# SCH_05_USB_To_TTL.net
KiCad netlist of a schematic drawn in Altium Designer
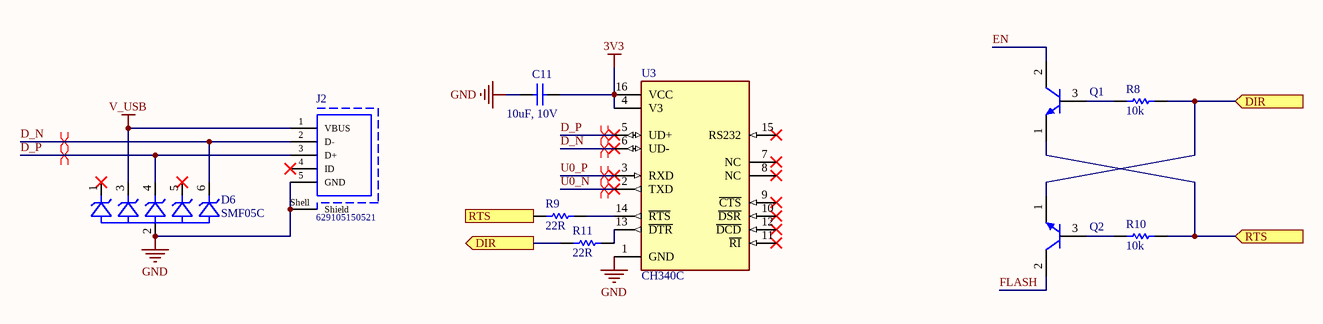
[diagram p0: SCH_05_USB_To_TTL.SchDoc]

(export (version "E")
  (design (tool "Eeschema 10.0.6"))
  (components
    (comp (ref "C11")
      (value "10uF, 10V")
      (footprint "WCAP-CSGP_0603_H=0.8mm_Reflow")
      (description "WCAP-CSGP Multilayer Ceramic Chip Capacitor, General Purpose, size 0603, X7R, 100nF, 10V")
      (fields
        (field (name "MANUFACTURER PART NUMBER") "885012206020")
        (field (name "MANUFACTURER") "Wurth Elektronik")
      )
      (libsource (lib "Altium_WCAP-CSGP (rev20a)") (part "885012206020"))
    )
    (comp (ref "D6")
      (value "SMF05C")
      (footprint "SC70-6")
      (description "12.5V Clamp 8A (8/20Âµs) Ipp Tvs Diode Surface Mount SC-88/SC70-6/SOT-363")
      (fields (field (name "MF") "ProTek Devices"))
      (libsource (lib "SMF05C") (part "SMF05C"))
    )
    (comp (ref "J2")
      (value "629105150521")
      (footprint "629105150521")
      (description "Micro USB 2.0 Type B Receptacle WR-COM, Horizontal, SMT, with Pegs, High Current at Pin 1 & Pin 5")
      (fields (field (name "PUBLISHER") "Wurth Elektronik"))
      (libsource (lib "ALTIUM-WR-COM_USB_20-rev18d") (part "629105150521"))
    )
    (comp (ref "Q1")
      (value "C1815")
      (footprint "SOT23B")
      (description "NPN Bipolar Transistor")
      (libsource (lib "PIF_Library") (part "C1815"))
    )
    (comp (ref "Q2")
      (value "C1815")
      (footprint "SOT23B")
      (description "NPN Bipolar Transistor")
      (libsource (lib "PIF_Library") (part "C1815"))
    )
    (comp (ref "R8")
      (value "10k")
      (footprint "RES-SM-0603")
      (description "Resistor")
      (fields (field (name "Comment") "RESISTOR SMD"))
      (libsource (lib "PIF_Library") (part "RESISTOR SMD"))
    )
    (comp (ref "R9")
      (value "22R")
      (footprint "RES-SM-0603")
      (description "Resistor")
      (fields (field (name "Comment") "RESISTOR SMD"))
      (libsource (lib "PIF_Library") (part "RESISTOR SMD"))
    )
    (comp (ref "R10")
      (value "10k")
      (footprint "RES-SM-0603")
      (description "Resistor")
      (fields (field (name "Comment") "RESISTOR SMD"))
      (libsource (lib "PIF_Library") (part "RESISTOR SMD"))
    )
    (comp (ref "R11")
      (value "22R")
      (footprint "RES-SM-0603")
      (description "Resistor")
      (fields (field (name "Comment") "RESISTOR SMD"))
      (libsource (lib "PIF_Library") (part "RESISTOR SMD"))
    )
    (comp (ref "U3")
      (value "CH340C")
      (footprint "SOIC127P600X180-16N")
      (libsource (lib "CH340") (part "CH340C"))
    )
  )
  (nets
    (net (code "1") (name "/DIR") (class "Default")
      (node (ref "Q2") (pin "1") (pinfunction "E_1") (pintype "passive"))
      (node (ref "R11") (pin "1") (pinfunction "1_1") (pintype "passive"))
      (node (ref "R8") (pin "2") (pinfunction "2_2") (pintype "passive"))
    )
    (net (code "2") (name "/D_N") (class "Default")
      (node (ref "D6") (pin "6") (pinfunction "C5_6") (pintype "passive"))
      (node (ref "J2") (pin "2") (pinfunction "D-_2") (pintype "passive"))
      (node (ref "U3") (pin "6") (pinfunction "UD-_6") (pintype "bidirectional"))
    )
    (net (code "3") (name "/D_P") (class "Default")
      (node (ref "D6") (pin "4") (pinfunction "C3_4") (pintype "passive"))
      (node (ref "J2") (pin "3") (pinfunction "D+_3") (pintype "passive"))
      (node (ref "U3") (pin "5") (pinfunction "UD+_5") (pintype "bidirectional"))
    )
    (net (code "4") (name "/EN") (class "Default")
      (node (ref "Q1") (pin "2") (pinfunction "C_2") (pintype "passive"))
    )
    (net (code "5") (name "/FLASH") (class "Default")
      (node (ref "Q2") (pin "2") (pinfunction "C_2") (pintype "passive"))
    )
    (net (code "6") (name "/RTS") (class "Default")
      (node (ref "Q1") (pin "1") (pinfunction "E_1") (pintype "passive"))
      (node (ref "R10") (pin "2") (pinfunction "2_2") (pintype "passive"))
      (node (ref "R9") (pin "1") (pinfunction "1_1") (pintype "passive"))
    )
    (net (code "7") (name "/U0_N") (class "Default")
      (node (ref "U3") (pin "2") (pinfunction "TXD_2") (pintype "output+no_connect"))
    )
    (net (code "8") (name "/U0_P") (class "Default")
      (node (ref "U3") (pin "3") (pinfunction "RXD_3") (pintype "input+no_connect"))
    )
    (net (code "9") (name "3V3") (class "Default")
      (node (ref "C11") (pin "2") (pinfunction "2_2") (pintype "passive"))
      (node (ref "U3") (pin "16") (pinfunction "VCC_16") (pintype "power_in"))
      (node (ref "U3") (pin "4") (pinfunction "V3_4") (pintype "power_in"))
    )
    (net (code "10") (name "GND") (class "Default")
      (node (ref "C11") (pin "1") (pinfunction "1_1") (pintype "passive"))
      (node (ref "D6") (pin "2") (pinfunction "A_2") (pintype "passive"))
      (node (ref "J2") (pin "5") (pinfunction "GND_5") (pintype "passive"))
      (node (ref "J2") (pin "Shell") (pinfunction "Shield_Shell") (pintype "passive"))
      (node (ref "U3") (pin "1") (pinfunction "GND_1") (pintype "power_in"))
    )
    (net (code "11") (name "Net-(Q1-B)") (class "Default")
      (node (ref "Q1") (pin "3") (pinfunction "B_3") (pintype "passive"))
      (node (ref "R8") (pin "1") (pinfunction "1_1") (pintype "passive"))
    )
    (net (code "12") (name "Net-(Q2-B)") (class "Default")
      (node (ref "Q2") (pin "3") (pinfunction "B_3") (pintype "passive"))
      (node (ref "R10") (pin "1") (pinfunction "1_1") (pintype "passive"))
    )
    (net (code "13") (name "Net-(U3-~{DTR})") (class "Default")
      (node (ref "R11") (pin "2") (pinfunction "2_2") (pintype "passive"))
      (node (ref "U3") (pin "13") (pinfunction "~{DTR}_13") (pintype "output"))
    )
    (net (code "14") (name "Net-(U3-~{RTS})") (class "Default")
      (node (ref "R9") (pin "2") (pinfunction "2_2") (pintype "passive"))
      (node (ref "U3") (pin "14") (pinfunction "~{RTS}_14") (pintype "output"))
    )
    (net (code "15") (name "V_USB") (class "Default")
      (node (ref "D6") (pin "3") (pinfunction "C2_3") (pintype "passive"))
      (node (ref "J2") (pin "1") (pinfunction "VBUS_1") (pintype "passive"))
    )
    (net (code "16") (name "unconnected-(D6-C1-Pad1)") (class "Default")
      (node (ref "D6") (pin "1") (pinfunction "C1_1") (pintype "passive+no_connect"))
    )
    (net (code "17") (name "unconnected-(D6-C4-Pad5)") (class "Default")
      (node (ref "D6") (pin "5") (pinfunction "C4_5") (pintype "passive+no_connect"))
    )
    (net (code "18") (name "unconnected-(J2-ID-Pad4)") (class "Default")
      (node (ref "J2") (pin "4") (pinfunction "ID_4") (pintype "passive+no_connect"))
    )
    (net (code "19") (name "unconnected-(U3-NC-Pad7)") (class "Default")
      (node (ref "U3") (pin "7") (pinfunction "NC_7") (pintype "power_in+no_connect"))
    )
    (net (code "20") (name "unconnected-(U3-NC-Pad8)") (class "Default")
      (node (ref "U3") (pin "8") (pinfunction "NC_8") (pintype "power_in+no_connect"))
    )
    (net (code "21") (name "unconnected-(U3-RS232-Pad15)") (class "Default")
      (node (ref "U3") (pin "15") (pinfunction "RS232_15") (pintype "input+no_connect"))
    )
    (net (code "22") (name "unconnected-(U3-~{CTS}-Pad9)") (class "Default")
      (node (ref "U3") (pin "9") (pinfunction "~{CTS}_9") (pintype "input+no_connect"))
    )
    (net (code "23") (name "unconnected-(U3-~{DCD}-Pad12)") (class "Default")
      (node (ref "U3") (pin "12") (pinfunction "~{DCD}_12") (pintype "input+no_connect"))
    )
    (net (code "24") (name "unconnected-(U3-~{DSR}-Pad10)") (class "Default")
      (node (ref "U3") (pin "10") (pinfunction "~{DSR}_10") (pintype "input+no_connect"))
    )
    (net (code "25") (name "unconnected-(U3-~{RI}-Pad11)") (class "Default")
      (node (ref "U3") (pin "11") (pinfunction "~{RI}_11") (pintype "input+no_connect"))
    )
  )
)
